# pwm2can.net
KiCad netlist of a schematic drawn in Altium Designer
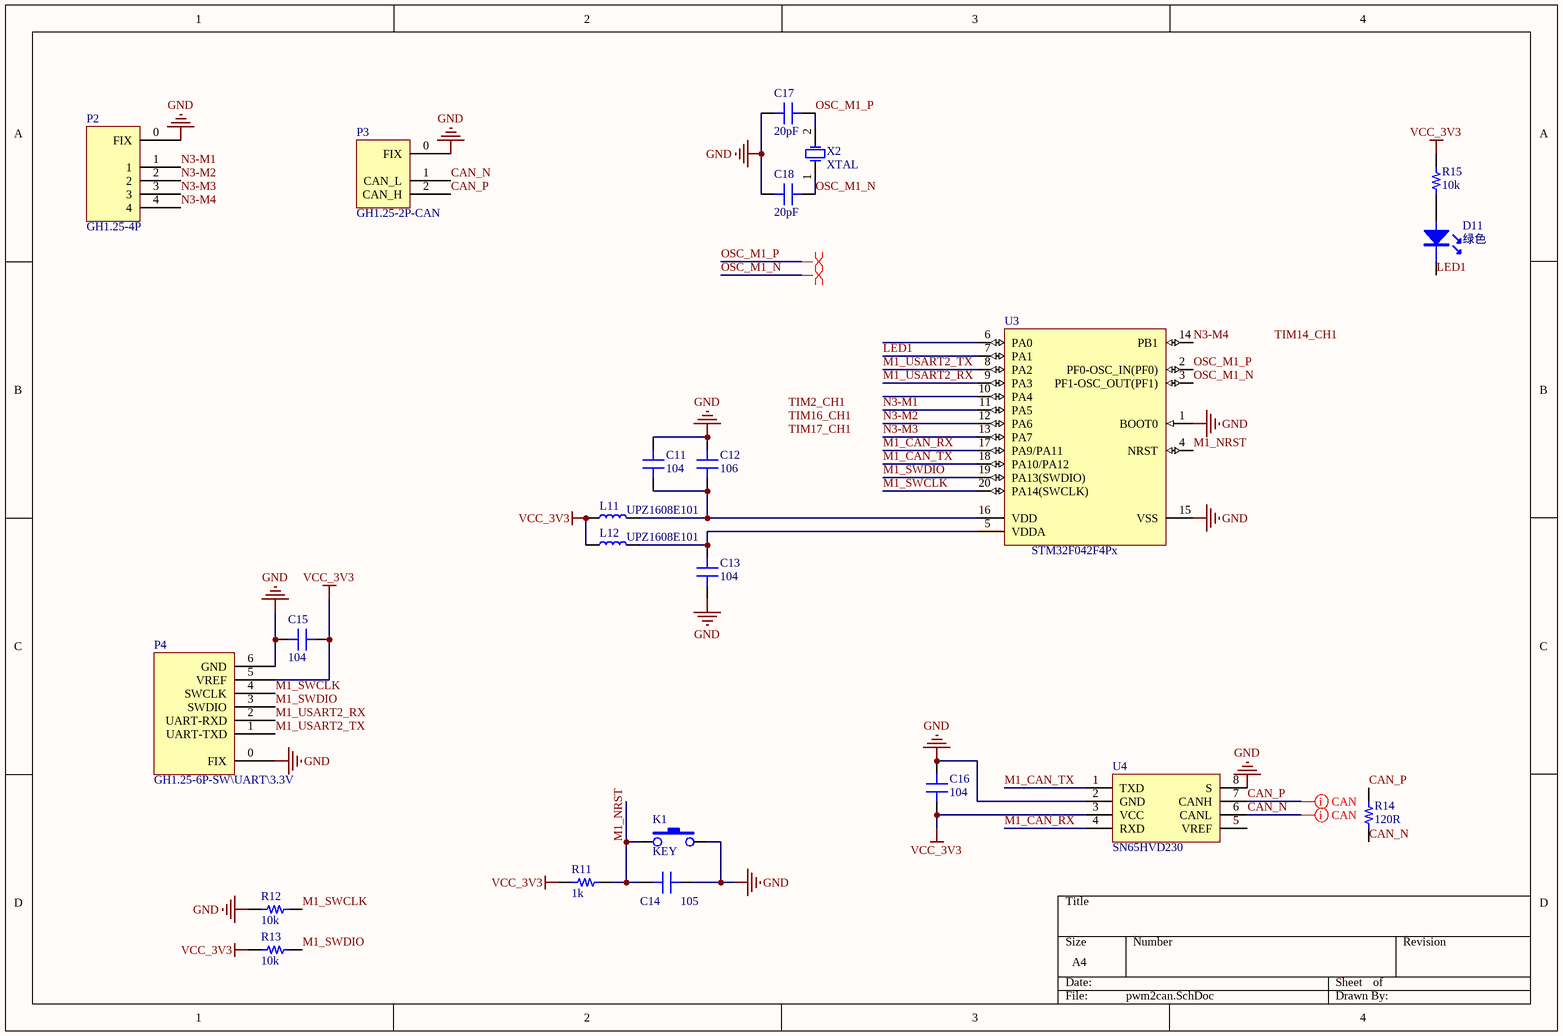
[diagram p0: pwm2can.SchDoc]

(export (version "E")
  (design (tool "Eeschema 10.0.6"))
  (components
    (comp (ref "C11")
      (value "104")
      (footprint "C0603/1608")
      (description "陶瓷电容")
      (libsource (lib "WMJ2019_Devices") (part "陶瓷电容"))
    )
    (comp (ref "C12")
      (value "106")
      (footprint "C0603/1608")
      (description "陶瓷电容")
      (libsource (lib "WMJ2019_Devices") (part "陶瓷电容"))
    )
    (comp (ref "C13")
      (value "104")
      (footprint "C0603/1608")
      (description "陶瓷电容")
      (libsource (lib "WMJ2019_Devices") (part "陶瓷电容"))
    )
    (comp (ref "C14")
      (value "105")
      (footprint "C0603/1608")
      (description "陶瓷电容")
      (libsource (lib "WMJ2019_Devices") (part "陶瓷电容"))
    )
    (comp (ref "C15")
      (value "104")
      (footprint "C0603/1608")
      (description "陶瓷电容")
      (libsource (lib "WMJ2019_Devices") (part "陶瓷电容"))
    )
    (comp (ref "C16")
      (value "104")
      (footprint "C0603/1608")
      (description "陶瓷电容")
      (libsource (lib "WMJ2019_Devices") (part "陶瓷电容"))
    )
    (comp (ref "C17")
      (value "20pF")
      (footprint "C0603/1608")
      (description "陶瓷电容")
      (libsource (lib "Devices") (part "陶瓷电容"))
    )
    (comp (ref "C18")
      (value "20pF")
      (footprint "C0603/1608")
      (description "陶瓷电容")
      (libsource (lib "Devices") (part "陶瓷电容"))
    )
    (comp (ref "D11")
      (value "LED-绿色")
      (footprint "LED0603-蓝色")
      (description "发光二极管")
      (fields (field (name "COLOR") "绿色"))
      (libsource (lib "Devices") (part "LED"))
    )
    (comp (ref "K1")
      (value "KEY")
      (footprint "按键（2脚）")
      (description "按键-2脚贴片")
      (libsource (lib "Devices") (part "按键（2脚）"))
    )
    (comp (ref "L11")
      (value "UPZ1608E101")
      (footprint "L0603/1608")
      (description "贴片磁珠")
      (libsource (lib "WMJ2019_Devices") (part "磁珠"))
    )
    (comp (ref "L12")
      (value "UPZ1608E101")
      (footprint "L0603/1608")
      (description "贴片磁珠")
      (libsource (lib "WMJ2019_Devices") (part "磁珠"))
    )
    (comp (ref "P2")
      (value "GH1.25-4P")
      (footprint "GH1.25-4P（卧贴）")
      (description "GH1.25-4P-CAN\\5V")
      (libsource (lib "Connectors") (part "GH1.25-4P"))
    )
    (comp (ref "P3")
      (value "GH1.25-2P-CAN")
      (footprint "GH1.25-2P（卧贴）")
      (libsource (lib "Connectors") (part "GH1.25-2P-CAN"))
    )
    (comp (ref "P4")
      (value "GH1.25-6P-S~{W}UAR~{T}3.3V")
      (footprint "GH1.25-6P（立贴）")
      (description "GH1.25-6P-SW\\UART\\3.3V")
      (libsource (lib "Connectors") (part "GH1.25-6P-SW{backslash}UART{backslash}3.3V"))
    )
    (comp (ref "R11")
      (value "1k")
      (footprint "R0603/1608")
      (description "电阻")
      (libsource (lib "WMJ2019_Devices") (part "电阻"))
    )
    (comp (ref "R12")
      (value "10k")
      (footprint "R0603/1608")
      (description "电阻")
      (libsource (lib "WMJ2019_Devices") (part "电阻"))
    )
    (comp (ref "R13")
      (value "10k")
      (footprint "R0603/1608")
      (description "电阻")
      (libsource (lib "WMJ2019_Devices") (part "电阻"))
    )
    (comp (ref "R14")
      (value "120R")
      (footprint "R0603/1608")
      (description "电阻")
      (libsource (lib "WMJ2019_Devices") (part "电阻"))
    )
    (comp (ref "R15")
      (value "10k")
      (footprint "R0603/1608")
      (description "电阻")
      (libsource (lib "WMJ2019_Devices") (part "电阻"))
    )
    (comp (ref "U3")
      (value "STM32F042F4Px")
      (footprint "TSSOP20")
      (libsource (lib "Devices") (part "STM32F042F4Px"))
    )
    (comp (ref "U4")
      (value "SN65HVD230")
      (footprint "SOP-8")
      (description "CAN收发芯片")
      (libsource (lib "WMJ2019_Devices") (part "SN65HVD230"))
    )
    (comp (ref "X2")
      (value "XTAL")
      (footprint "XTAL-49S")
      (description "晶振")
      (fields (field (name "PUBLISHER") "Altium Limited"))
      (libsource (lib "Devices") (part "晶振"))
    )
  )
  (nets
    (net (code "1") (name "/CAN_N") (class "Default")
      (node (ref "P3") (pin "1") (pinfunction "CAN_L_1") (pintype "passive"))
      (node (ref "R14") (pin "1") (pintype "passive"))
      (node (ref "U4") (pin "6") (pinfunction "CANL_6") (pintype "passive"))
    )
    (net (code "2") (name "/CAN_P") (class "Default")
      (node (ref "P3") (pin "2") (pinfunction "CAN_H_2") (pintype "passive"))
      (node (ref "R14") (pin "2") (pintype "passive"))
      (node (ref "U4") (pin "7") (pinfunction "CANH_7") (pintype "passive"))
    )
    (net (code "3") (name "/LED1") (class "Default")
      (node (ref "D11") (pin "2") (pinfunction "K_2") (pintype "passive"))
      (node (ref "U3") (pin "7") (pinfunction "PA1_7") (pintype "bidirectional"))
    )
    (net (code "4") (name "/M1_CAN_RX") (class "Default")
      (node (ref "U3") (pin "17") (pinfunction "PA9/PA11_17") (pintype "bidirectional"))
      (node (ref "U4") (pin "4") (pinfunction "RXD_4") (pintype "passive"))
    )
    (net (code "5") (name "/M1_CAN_TX") (class "Default")
      (node (ref "U3") (pin "18") (pinfunction "PA10/PA12_18") (pintype "bidirectional"))
      (node (ref "U4") (pin "1") (pinfunction "TXD_1") (pintype "passive"))
    )
    (net (code "6") (name "/M1_NRST") (class "Default")
      (node (ref "C14") (pin "2") (pintype "passive"))
      (node (ref "K1") (pin "1") (pintype "passive"))
      (node (ref "R11") (pin "2") (pintype "passive"))
      (node (ref "U3") (pin "4") (pinfunction "NRST_4") (pintype "bidirectional"))
    )
    (net (code "7") (name "/M1_SWCLK") (class "Default")
      (node (ref "P4") (pin "4") (pinfunction "SWCLK_4") (pintype "passive"))
      (node (ref "R12") (pin "2") (pintype "passive"))
      (node (ref "U3") (pin "20") (pinfunction "PA14(SWCLK)_20") (pintype "bidirectional"))
    )
    (net (code "8") (name "/M1_SWDIO") (class "Default")
      (node (ref "P4") (pin "3") (pinfunction "SWDIO_3") (pintype "passive"))
      (node (ref "R13") (pin "2") (pintype "passive"))
      (node (ref "U3") (pin "19") (pinfunction "PA13(SWDIO)_19") (pintype "bidirectional"))
    )
    (net (code "9") (name "/M1_USART2_RX") (class "Default")
      (node (ref "P4") (pin "2") (pinfunction "UART-RXD_2") (pintype "passive"))
      (node (ref "U3") (pin "9") (pinfunction "PA3_9") (pintype "bidirectional"))
    )
    (net (code "10") (name "/M1_USART2_TX") (class "Default")
      (node (ref "P4") (pin "1") (pinfunction "UART-TXD_1") (pintype "passive"))
      (node (ref "U3") (pin "8") (pinfunction "PA2_8") (pintype "bidirectional"))
    )
    (net (code "11") (name "/N3-M1") (class "Default")
      (node (ref "P2") (pin "1") (pinfunction "1_1") (pintype "passive"))
      (node (ref "U3") (pin "11") (pinfunction "PA5_11") (pintype "bidirectional"))
    )
    (net (code "12") (name "/N3-M2") (class "Default")
      (node (ref "P2") (pin "2") (pinfunction "2_2") (pintype "passive"))
      (node (ref "U3") (pin "12") (pinfunction "PA6_12") (pintype "bidirectional"))
    )
    (net (code "13") (name "/N3-M3") (class "Default")
      (node (ref "P2") (pin "3") (pinfunction "3_3") (pintype "passive"))
      (node (ref "U3") (pin "13") (pinfunction "PA7_13") (pintype "bidirectional"))
    )
    (net (code "14") (name "/N3-M4") (class "Default")
      (node (ref "P2") (pin "4") (pinfunction "4_4") (pintype "passive"))
      (node (ref "U3") (pin "14") (pinfunction "PB1_14") (pintype "bidirectional"))
    )
    (net (code "15") (name "/OSC_M1_N") (class "Default")
      (node (ref "C18") (pin "1") (pintype "passive"))
      (node (ref "U3") (pin "3") (pinfunction "PF1-OSC_OUT(PF1)_3") (pintype "bidirectional"))
      (node (ref "X2") (pin "1") (pinfunction "OSC1_1") (pintype "passive"))
    )
    (net (code "16") (name "/OSC_M1_P") (class "Default")
      (node (ref "C17") (pin "1") (pintype "passive"))
      (node (ref "U3") (pin "2") (pinfunction "PF0-OSC_IN(PF0)_2") (pintype "bidirectional"))
      (node (ref "X2") (pin "2") (pinfunction "OSC2_2") (pintype "passive"))
    )
    (net (code "21") (name "GND") (class "Default")
      (node (ref "C11") (pin "1") (pintype "passive"))
      (node (ref "C12") (pin "1") (pintype "passive"))
      (node (ref "C13") (pin "1") (pintype "passive"))
      (node (ref "C14") (pin "1") (pintype "passive"))
      (node (ref "C15") (pin "2") (pintype "passive"))
      (node (ref "C16") (pin "2") (pintype "passive"))
      (node (ref "C17") (pin "2") (pintype "passive"))
      (node (ref "C18") (pin "2") (pintype "passive"))
      (node (ref "K1") (pin "2") (pintype "passive"))
      (node (ref "P2") (pin "0") (pinfunction "FIX_0") (pintype "passive"))
      (node (ref "P3") (pin "0") (pinfunction "FIX_0") (pintype "passive"))
      (node (ref "P4") (pin "0") (pinfunction "FIX_0") (pintype "passive"))
      (node (ref "P4") (pin "6") (pinfunction "GND_6") (pintype "passive"))
      (node (ref "R12") (pin "1") (pintype "passive"))
      (node (ref "U3") (pin "1") (pinfunction "BOOT0_1") (pintype "input"))
      (node (ref "U3") (pin "15") (pinfunction "VSS_15") (pintype "power_in"))
      (node (ref "U4") (pin "2") (pinfunction "GND_2") (pintype "passive"))
      (node (ref "U4") (pin "8") (pinfunction "S_8") (pintype "passive"))
    )
    (net (code "22") (name "Net-(D11-A)") (class "Default")
      (node (ref "D11") (pin "1") (pinfunction "A_1") (pintype "passive"))
      (node (ref "R15") (pin "1") (pintype "passive"))
    )
    (net (code "23") (name "Net-(U3-VDD)") (class "Default")
      (node (ref "C11") (pin "2") (pintype "passive"))
      (node (ref "C12") (pin "2") (pintype "passive"))
      (node (ref "L11") (pin "2") (pinfunction "2_2") (pintype "passive"))
      (node (ref "U3") (pin "16") (pinfunction "VDD_16") (pintype "power_in"))
    )
    (net (code "24") (name "Net-(U3-VDDA)") (class "Default")
      (node (ref "C13") (pin "2") (pintype "passive"))
      (node (ref "L12") (pin "2") (pinfunction "2_2") (pintype "passive"))
      (node (ref "U3") (pin "5") (pinfunction "VDDA_5") (pintype "power_in"))
    )
    (net (code "25") (name "VCC_3V3") (class "Default")
      (node (ref "C15") (pin "1") (pintype "passive"))
      (node (ref "C16") (pin "1") (pintype "passive"))
      (node (ref "L11") (pin "1") (pinfunction "1_1") (pintype "passive"))
      (node (ref "L12") (pin "1") (pinfunction "1_1") (pintype "passive"))
      (node (ref "P4") (pin "5") (pinfunction "VREF_5") (pintype "passive"))
      (node (ref "R11") (pin "1") (pintype "passive"))
      (node (ref "R13") (pin "1") (pintype "passive"))
      (node (ref "R15") (pin "2") (pintype "passive"))
      (node (ref "U4") (pin "3") (pinfunction "VCC_3") (pintype "passive"))
    )
    (net (code "26") (name "unconnected-(U3-PA0-Pad6)") (class "Default")
      (node (ref "U3") (pin "6") (pinfunction "PA0_6") (pintype "bidirectional"))
    )
    (net (code "27") (name "unconnected-(U3-PA4-Pad10)") (class "Default")
      (node (ref "U3") (pin "10") (pinfunction "PA4_10") (pintype "bidirectional"))
    )
    (net (code "28") (name "unconnected-(U4-VREF-Pad5)") (class "Default")
      (node (ref "U4") (pin "5") (pinfunction "VREF_5") (pintype "passive"))
    )
  )
)
